# pyra_dvt1_power-2_1.net
KiCad netlist of a schematic drawn in Altium Designer
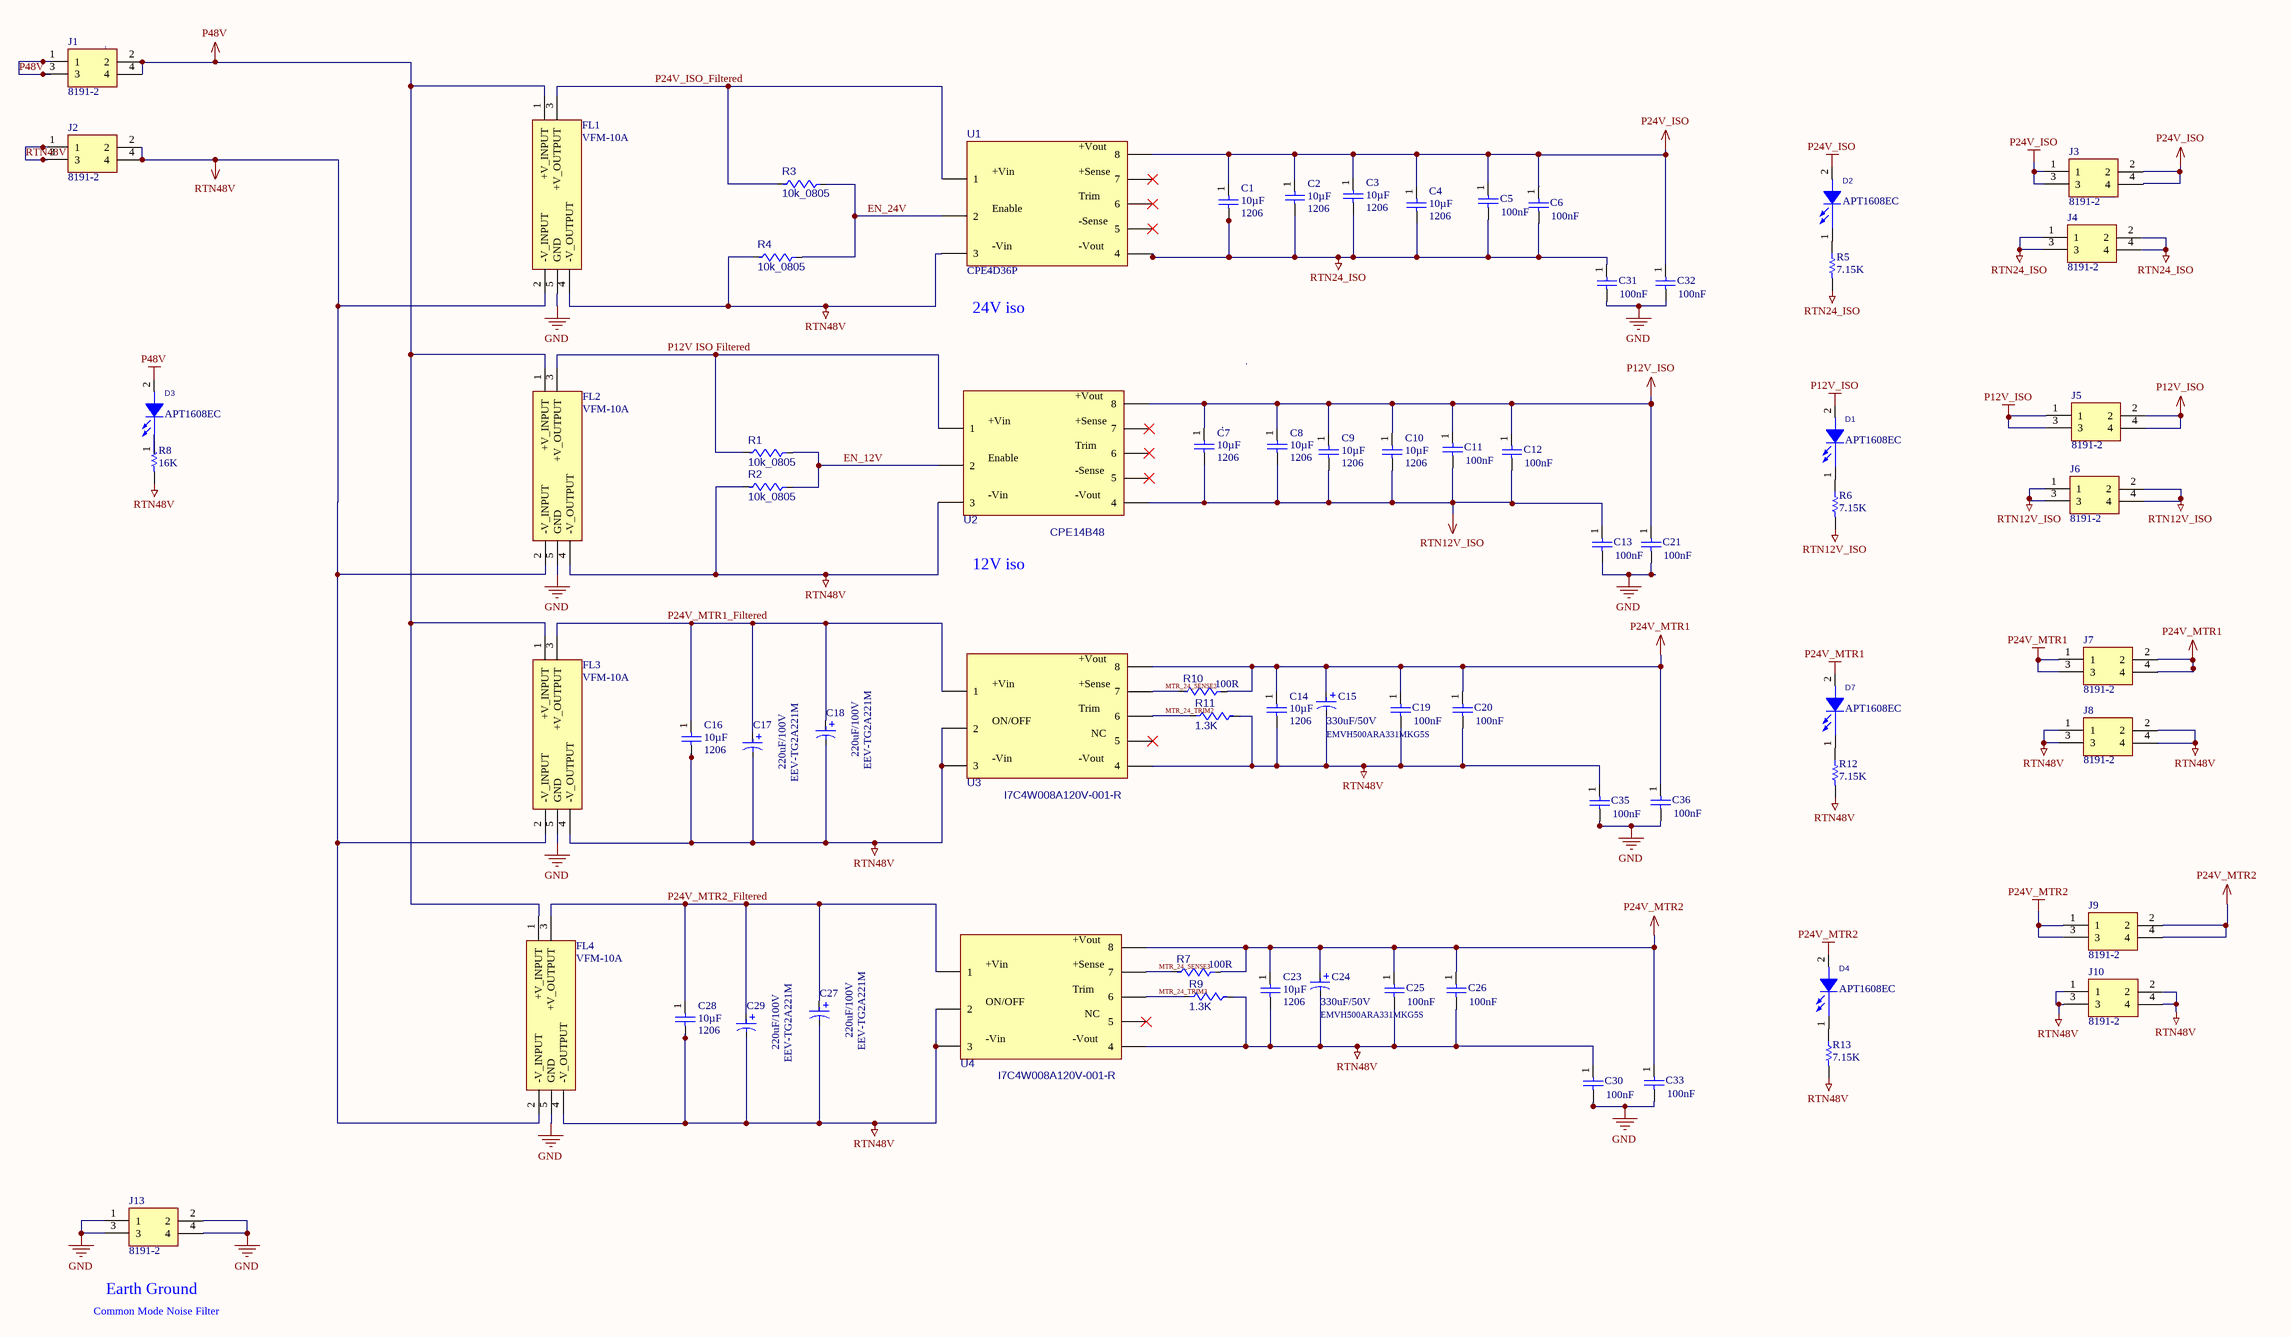
[diagram p0: pyra_dvt1_power-2.1.SchDoc]

(export (version "E")
  (design (tool "Eeschema 10.0.6"))
  (components
    (comp (ref "C1")
      (value "10µF")
      (footprint "1206")
      (description "CAP CER 10UF 50V X5R 1206")
      (fields
        (field (name "MANUFACTURER") "TDK Corporation")
        (field (name "TOLERANCE") "±20%")
        (field (name "SIZE") "1206")
      )
      (libsource (lib "bct") (part "C1206_10UF_50V"))
    )
    (comp (ref "C2")
      (value "10µF")
      (footprint "1206")
      (description "CAP CER 10UF 50V X5R 1206")
      (fields
        (field (name "MANUFACTURER") "TDK Corporation")
        (field (name "TOLERANCE") "±20%")
        (field (name "SIZE") "1206")
      )
      (libsource (lib "bct") (part "C1206_10UF_50V"))
    )
    (comp (ref "C3")
      (value "10µF")
      (footprint "1206")
      (description "CAP CER 10UF 50V X5R 1206")
      (fields
        (field (name "MANUFACTURER") "TDK Corporation")
        (field (name "TOLERANCE") "±20%")
        (field (name "SIZE") "1206")
      )
      (libsource (lib "bct") (part "C1206_10UF_50V"))
    )
    (comp (ref "C4")
      (value "10µF")
      (footprint "1206")
      (description "CAP CER 10UF 50V X5R 1206")
      (fields
        (field (name "MANUFACTURER") "TDK Corporation")
        (field (name "TOLERANCE") "±20%")
        (field (name "SIZE") "1206")
      )
      (libsource (lib "bct") (part "C1206_10UF_50V"))
    )
    (comp (ref "C5")
      (value "100nF")
      (footprint "0603R(1608)")
      (description "CAP CER 0.1UF 50V X5R 0603")
      (fields (field (name "MANUFACTURER") "TDK Corporation") (field (name "TOLERANCE") "±10%"))
      (libsource (lib "bct") (part "C0603_100NF_50V"))
    )
    (comp (ref "C6")
      (value "100nF")
      (footprint "0603R(1608)")
      (description "CAP CER 0.1UF 50V X5R 0603")
      (fields (field (name "MANUFACTURER") "TDK Corporation") (field (name "TOLERANCE") "±10%"))
      (libsource (lib "bct") (part "C0603_100NF_50V"))
    )
    (comp (ref "C7")
      (value "10µF")
      (footprint "1206")
      (description "CAP CER 10UF 50V X5R 1206")
      (fields
        (field (name "MANUFACTURER") "TDK Corporation")
        (field (name "TOLERANCE") "±20%")
        (field (name "SIZE") "1206")
      )
      (libsource (lib "bct") (part "C1206_10UF_50V"))
    )
    (comp (ref "C8")
      (value "10µF")
      (footprint "1206")
      (description "CAP CER 10UF 50V X5R 1206")
      (fields
        (field (name "MANUFACTURER") "TDK Corporation")
        (field (name "TOLERANCE") "±20%")
        (field (name "SIZE") "1206")
      )
      (libsource (lib "bct") (part "C1206_10UF_50V"))
    )
    (comp (ref "C9")
      (value "10µF")
      (footprint "1206")
      (description "CAP CER 10UF 50V X5R 1206")
      (fields
        (field (name "MANUFACTURER") "TDK Corporation")
        (field (name "TOLERANCE") "±20%")
        (field (name "SIZE") "1206")
      )
      (libsource (lib "bct") (part "C1206_10UF_50V"))
    )
    (comp (ref "C10")
      (value "10µF")
      (footprint "1206")
      (description "CAP CER 10UF 50V X5R 1206")
      (fields
        (field (name "MANUFACTURER") "TDK Corporation")
        (field (name "TOLERANCE") "±20%")
        (field (name "SIZE") "1206")
      )
      (libsource (lib "bct") (part "C1206_10UF_50V"))
    )
    (comp (ref "C11")
      (value "100nF")
      (footprint "0603R(1608)")
      (description "CAP CER 0.1UF 50V X5R 0603")
      (fields (field (name "MANUFACTURER") "TDK Corporation") (field (name "TOLERANCE") "±10%"))
      (libsource (lib "bct") (part "C0603_100NF_50V"))
    )
    (comp (ref "C12")
      (value "100nF")
      (footprint "0603R(1608)")
      (description "CAP CER 0.1UF 50V X5R 0603")
      (fields (field (name "MANUFACTURER") "TDK Corporation") (field (name "TOLERANCE") "±10%"))
      (libsource (lib "bct") (part "C0603_100NF_50V"))
    )
    (comp (ref "C13")
      (value "100nF")
      (footprint "0603R(1608)")
      (description "CAP CER 0.1UF 50V X5R 0603")
      (fields (field (name "MANUFACTURER") "TDK Corporation") (field (name "TOLERANCE") "±10%"))
      (libsource (lib "bct") (part "C0603_100NF_50V"))
    )
    (comp (ref "C14")
      (value "10µF")
      (footprint "1206")
      (description "CAP CER 10UF 50V X5R 1206")
      (fields
        (field (name "MANUFACTURER") "TDK Corporation")
        (field (name "TOLERANCE") "±20%")
        (field (name "SIZE") "1206")
      )
      (libsource (lib "bct") (part "C1206_10UF_50V"))
    )
    (comp (ref "C15")
      (value "330uF/50V")
      (footprint "EMVH500ARA331MKG5S")
      (description "CAP ALUM 330UF 20% 50V SMD")
      (fields
        (field (name "MANUFACTURER") "United Chemi-con")
        (field (name "MANUFACTURER PART NUMBER") "EMVH500ARA331MKG5S")
        (field (name "TOLERANCE") "20%")
        (field (name "_VERIFIED FOOTPRINT") ".mfr-pn? footprint?")
        (field (name "_VERIFIED SYMBOL") ".mfr-pn?")
        (field (name "_VERIFIED BOM") ".mfr-pn?")
      )
      (libsource (lib "PowerPCB") (part "CAP POLAR  330uF"))
    )
    (comp (ref "C16")
      (value "10µF")
      (footprint "1206")
      (description "CAP CER 10UF 50V X5R 1206")
      (fields
        (field (name "MANUFACTURER") "TDK Corporation")
        (field (name "TOLERANCE") "±20%")
        (field (name "SIZE") "1206")
      )
      (libsource (lib "bct") (part "C1206_10UF_50V"))
    )
    (comp (ref "C17")
      (value "220uF/100V")
      (footprint "EMVH101GDA221MMN0S")
      (description "CAP ALUM 220UF 20% 100V SMD")
      (fields
        (field (name "MANUFACTURER") "Panasonic")
        (field (name "MANUFACTURER PART NUMBER") "EEV-TG2A221M")
        (field (name "TOLERANCE") "20%")
        (field (name "_VERIFIED FOOTPRINT") ".mfr-pn? footprint?")
        (field (name "_VERIFIED SYMBOL") ".mfr-pn?")
        (field (name "_VERIFIED BOM") ".mfr-pn?")
      )
      (libsource (lib "PowerPCB") (part "CAP POLAR  220uF"))
    )
    (comp (ref "C18")
      (value "220uF/100V")
      (footprint "EMVH101GDA221MMN0S")
      (description "CAP ALUM 220UF 20% 100V SMD")
      (fields
        (field (name "MANUFACTURER") "Panasonic")
        (field (name "MANUFACTURER PART NUMBER") "EEV-TG2A221M")
        (field (name "TOLERANCE") "20%")
        (field (name "_VERIFIED FOOTPRINT") ".mfr-pn? footprint?")
        (field (name "_VERIFIED SYMBOL") ".mfr-pn?")
        (field (name "_VERIFIED BOM") ".mfr-pn?")
      )
      (libsource (lib "PowerPCB") (part "CAP POLAR  220uF"))
    )
    (comp (ref "C19")
      (value "100nF")
      (footprint "0603R(1608)")
      (description "CAP CER 0.1UF 50V X5R 0603")
      (fields (field (name "MANUFACTURER") "TDK Corporation") (field (name "TOLERANCE") "±10%"))
      (libsource (lib "bct") (part "C0603_100NF_50V"))
    )
    (comp (ref "C20")
      (value "100nF")
      (footprint "0603R(1608)")
      (description "CAP CER 0.1UF 50V X5R 0603")
      (fields (field (name "MANUFACTURER") "TDK Corporation") (field (name "TOLERANCE") "±10%"))
      (libsource (lib "bct") (part "C0603_100NF_50V"))
    )
    (comp (ref "C21")
      (value "100nF")
      (footprint "0603R(1608)")
      (description "CAP CER 0.1UF 50V X5R 0603")
      (fields (field (name "MANUFACTURER") "TDK Corporation") (field (name "TOLERANCE") "±10%"))
      (libsource (lib "bct") (part "C0603_100NF_50V"))
    )
    (comp (ref "C23")
      (value "10µF")
      (footprint "1206")
      (description "CAP CER 10UF 50V X5R 1206")
      (fields
        (field (name "MANUFACTURER") "TDK Corporation")
        (field (name "TOLERANCE") "±20%")
        (field (name "SIZE") "1206")
      )
      (libsource (lib "bct") (part "C1206_10UF_50V"))
    )
    (comp (ref "C24")
      (value "330uF/50V")
      (footprint "EMVH500ARA331MKG5S")
      (description "CAP ALUM 330UF 20% 50V SMD")
      (fields
        (field (name "MANUFACTURER") "United Chemi-con")
        (field (name "MANUFACTURER PART NUMBER") "EMVH500ARA331MKG5S")
        (field (name "TOLERANCE") "20%")
        (field (name "_VERIFIED FOOTPRINT") ".mfr-pn? footprint?")
        (field (name "_VERIFIED SYMBOL") ".mfr-pn?")
        (field (name "_VERIFIED BOM") ".mfr-pn?")
      )
      (libsource (lib "PowerPCB") (part "CAP POLAR  330uF"))
    )
    (comp (ref "C25")
      (value "100nF")
      (footprint "0603R(1608)")
      (description "CAP CER 0.1UF 50V X5R 0603")
      (fields (field (name "MANUFACTURER") "TDK Corporation") (field (name "TOLERANCE") "±10%"))
      (libsource (lib "bct") (part "C0603_100NF_50V"))
    )
    (comp (ref "C26")
      (value "100nF")
      (footprint "0603R(1608)")
      (description "CAP CER 0.1UF 50V X5R 0603")
      (fields (field (name "MANUFACTURER") "TDK Corporation") (field (name "TOLERANCE") "±10%"))
      (libsource (lib "bct") (part "C0603_100NF_50V"))
    )
    (comp (ref "C27")
      (value "220uF/100V")
      (footprint "EMVH101GDA221MMN0S")
      (description "CAP ALUM 220UF 20% 100V SMD")
      (fields
        (field (name "MANUFACTURER") "Panasonic")
        (field (name "MANUFACTURER PART NUMBER") "EEV-TG2A221M")
        (field (name "TOLERANCE") "20%")
        (field (name "_VERIFIED FOOTPRINT") ".mfr-pn? footprint?")
        (field (name "_VERIFIED SYMBOL") ".mfr-pn?")
        (field (name "_VERIFIED BOM") ".mfr-pn?")
      )
      (libsource (lib "PowerPCB") (part "CAP POLAR  220uF"))
    )
    (comp (ref "C28")
      (value "10µF")
      (footprint "1206")
      (description "CAP CER 10UF 50V X5R 1206")
      (fields
        (field (name "MANUFACTURER") "TDK Corporation")
        (field (name "TOLERANCE") "±20%")
        (field (name "SIZE") "1206")
      )
      (libsource (lib "bct") (part "C1206_10UF_50V"))
    )
    (comp (ref "C29")
      (value "220uF/100V")
      (footprint "EMVH101GDA221MMN0S")
      (description "CAP ALUM 220UF 20% 100V SMD")
      (fields
        (field (name "MANUFACTURER") "Panasonic")
        (field (name "MANUFACTURER PART NUMBER") "EEV-TG2A221M")
        (field (name "TOLERANCE") "20%")
        (field (name "_VERIFIED FOOTPRINT") ".mfr-pn? footprint?")
        (field (name "_VERIFIED SYMBOL") ".mfr-pn?")
        (field (name "_VERIFIED BOM") ".mfr-pn?")
      )
      (libsource (lib "PowerPCB") (part "CAP POLAR  220uF"))
    )
    (comp (ref "C30")
      (value "100nF")
      (footprint "0603R(1608)")
      (description "CAP CER 0.1UF 50V X5R 0603")
      (fields (field (name "MANUFACTURER") "TDK Corporation") (field (name "TOLERANCE") "±10%"))
      (libsource (lib "bct") (part "C0603_100NF_50V"))
    )
    (comp (ref "C31")
      (value "100nF")
      (footprint "0603R(1608)")
      (description "CAP CER 0.1UF 50V X5R 0603")
      (fields (field (name "MANUFACTURER") "TDK Corporation") (field (name "TOLERANCE") "±10%"))
      (libsource (lib "bct") (part "C0603_100NF_50V"))
    )
    (comp (ref "C32")
      (value "100nF")
      (footprint "0603R(1608)")
      (description "CAP CER 0.1UF 50V X5R 0603")
      (fields (field (name "MANUFACTURER") "TDK Corporation") (field (name "TOLERANCE") "±10%"))
      (libsource (lib "bct") (part "C0603_100NF_50V"))
    )
    (comp (ref "C33")
      (value "100nF")
      (footprint "0603R(1608)")
      (description "CAP CER 0.1UF 50V X5R 0603")
      (fields (field (name "MANUFACTURER") "TDK Corporation") (field (name "TOLERANCE") "±10%"))
      (libsource (lib "bct") (part "C0603_100NF_50V"))
    )
    (comp (ref "C35")
      (value "100nF")
      (footprint "0603R(1608)")
      (description "CAP CER 0.1UF 50V X5R 0603")
      (fields (field (name "MANUFACTURER") "TDK Corporation") (field (name "TOLERANCE") "±10%"))
      (libsource (lib "bct") (part "C0603_100NF_50V"))
    )
    (comp (ref "C36")
      (value "100nF")
      (footprint "0603R(1608)")
      (description "CAP CER 0.1UF 50V X5R 0603")
      (fields (field (name "MANUFACTURER") "TDK Corporation") (field (name "TOLERANCE") "±10%"))
      (libsource (lib "bct") (part "C0603_100NF_50V"))
    )
    (comp (ref "D1")
      (value "APT1608EC")
      (footprint "APT1608EC")
      (description "red, 0603")
      (fields
        (field (name "MANUFACTURER") "Kingbright")
        (field (name "MANUFACTURER PART NUMBER") "APT1608EC")
      )
      (libsource (lib "bct") (part "LED_red_0603"))
    )
    (comp (ref "D2")
      (value "APT1608EC")
      (footprint "APT1608EC")
      (description "red, 0603")
      (fields
        (field (name "MANUFACTURER") "Kingbright")
        (field (name "MANUFACTURER PART NUMBER") "APT1608EC")
      )
      (libsource (lib "bct") (part "LED_red_0603"))
    )
    (comp (ref "D3")
      (value "APT1608EC")
      (footprint "APT1608EC")
      (description "red, 0603")
      (fields
        (field (name "MANUFACTURER") "Kingbright")
        (field (name "MANUFACTURER PART NUMBER") "APT1608EC")
      )
      (libsource (lib "bct") (part "LED_red_0603"))
    )
    (comp (ref "D4")
      (value "APT1608EC")
      (footprint "APT1608EC")
      (description "red, 0603")
      (fields
        (field (name "MANUFACTURER") "Kingbright")
        (field (name "MANUFACTURER PART NUMBER") "APT1608EC")
      )
      (libsource (lib "bct") (part "LED_red_0603"))
    )
    (comp (ref "D7")
      (value "APT1608EC")
      (footprint "APT1608EC")
      (description "red, 0603")
      (fields
        (field (name "MANUFACTURER") "Kingbright")
        (field (name "MANUFACTURER PART NUMBER") "APT1608EC")
      )
      (libsource (lib "bct") (part "LED_red_0603"))
    )
    (comp (ref "FL1")
      (value "VFM-10A")
      (footprint "VFM10A")
      (description "Power Line Filters 0-75Vin 10A DC EMI Filter")
      (fields (field (name "MOUSER PART NUMBER") "490-VFM-10A"))
      (libsource (lib "Bellwether Coffee") (part "VFM-10A"))
    )
    (comp (ref "FL2")
      (value "VFM-10A")
      (footprint "VFM10A")
      (description "Power Line Filters 0-75Vin 10A DC EMI Filter")
      (fields (field (name "MOUSER PART NUMBER") "490-VFM-10A"))
      (libsource (lib "Bellwether Coffee") (part "VFM-10A"))
    )
    (comp (ref "FL3")
      (value "VFM-10A")
      (footprint "VFM10A")
      (description "Power Line Filters 0-75Vin 10A DC EMI Filter")
      (fields (field (name "MOUSER PART NUMBER") "490-VFM-10A"))
      (libsource (lib "Bellwether Coffee") (part "VFM-10A"))
    )
    (comp (ref "FL4")
      (value "VFM-10A")
      (footprint "VFM10A")
      (description "Power Line Filters 0-75Vin 10A DC EMI Filter")
      (fields (field (name "MOUSER PART NUMBER") "490-VFM-10A"))
      (libsource (lib "Bellwether Coffee") (part "VFM-10A"))
    )
    (comp (ref "J1")
      (value "8191-2")
      (footprint "81912")
      (description "Keystone, Brass Screw Terminal, 22  14 AWG, 15A")
      (fields (field (name "MOUSER PART NUMBER") "534-8191-2"))
      (libsource (lib "Bellwether Coffee") (part "8191-2"))
    )
    (comp (ref "J2")
      (value "8191-2")
      (footprint "81912")
      (description "Keystone, Brass Screw Terminal, 22  14 AWG, 15A")
      (fields (field (name "MOUSER PART NUMBER") "534-8191-2"))
      (libsource (lib "Bellwether Coffee") (part "8191-2"))
    )
    (comp (ref "J3")
      (value "8191-2")
      (footprint "81912")
      (description "Keystone, Brass Screw Terminal, 22  14 AWG, 15A")
      (fields (field (name "MOUSER PART NUMBER") "534-8191-2"))
      (libsource (lib "Bellwether Coffee") (part "8191-2"))
    )
    (comp (ref "J4")
      (value "8191-2")
      (footprint "81912")
      (description "Keystone, Brass Screw Terminal, 22  14 AWG, 15A")
      (fields (field (name "MOUSER PART NUMBER") "534-8191-2"))
      (libsource (lib "Bellwether Coffee") (part "8191-2"))
    )
    (comp (ref "J5")
      (value "8191-2")
      (footprint "81912")
      (description "Keystone, Brass Screw Terminal, 22  14 AWG, 15A")
      (fields (field (name "MOUSER PART NUMBER") "534-8191-2"))
      (libsource (lib "Bellwether Coffee") (part "8191-2"))
    )
    (comp (ref "J6")
      (value "8191-2")
      (footprint "81912")
      (description "Keystone, Brass Screw Terminal, 22  14 AWG, 15A")
      (fields (field (name "MOUSER PART NUMBER") "534-8191-2"))
      (libsource (lib "Bellwether Coffee") (part "8191-2"))
    )
    (comp (ref "J7")
      (value "8191-2")
      (footprint "81912")
      (description "Keystone, Brass Screw Terminal, 22  14 AWG, 15A")
      (fields (field (name "MOUSER PART NUMBER") "534-8191-2"))
      (libsource (lib "Bellwether Coffee") (part "8191-2"))
    )
    (comp (ref "J8")
      (value "8191-2")
      (footprint "81912")
      (description "Keystone, Brass Screw Terminal, 22  14 AWG, 15A")
      (fields (field (name "MOUSER PART NUMBER") "534-8191-2"))
      (libsource (lib "Bellwether Coffee") (part "8191-2"))
    )
    (comp (ref "J9")
      (value "8191-2")
      (footprint "81912")
      (description "Keystone, Brass Screw Terminal, 22  14 AWG, 15A")
      (fields (field (name "MOUSER PART NUMBER") "534-8191-2"))
      (libsource (lib "Bellwether Coffee") (part "8191-2"))
    )
    (comp (ref "J10")
      (value "8191-2")
      (footprint "81912")
      (description "Keystone, Brass Screw Terminal, 22  14 AWG, 15A")
      (fields (field (name "MOUSER PART NUMBER") "534-8191-2"))
      (libsource (lib "Bellwether Coffee") (part "8191-2"))
    )
    (comp (ref "J13")
      (value "8191-2")
      (footprint "81912")
      (description "Keystone, Brass Screw Terminal, 22  14 AWG, 15A")
      (fields (field (name "MOUSER PART NUMBER") "534-8191-2"))
      (libsource (lib "Bellwether Coffee") (part "8191-2"))
    )
    (comp (ref "R1")
      (value "10k_0805")
      (footprint "0805")
      (description "Res Thick Film 0805 10K Ohm 1% 0.125W ±100ppm/°C Molded SMD Paper T/R")
      (fields
        (field (name "MANUFACTURER") "Stackpole Electronics")
        (field (name "MANUFACTURER PART NUMBER") "RMCF0805FT10K0")
      )
      (libsource (lib "PowerPCB") (part "RES 10k_0805"))
    )
    (comp (ref "R2")
      (value "10k_0805")
      (footprint "0805")
      (description "Res Thick Film 0805 10K Ohm 1% 0.125W ±100ppm/°C Molded SMD Paper T/R")
      (fields
        (field (name "MANUFACTURER") "Stackpole Electronics")
        (field (name "MANUFACTURER PART NUMBER") "RMCF0805FT10K0")
      )
      (libsource (lib "PowerPCB") (part "RES 10k_0805"))
    )
    (comp (ref "R3")
      (value "10k_0805")
      (footprint "0805")
      (description "Res Thick Film 0805 10K Ohm 1% 0.125W ±100ppm/°C Molded SMD Paper T/R")
      (fields
        (field (name "MANUFACTURER") "Stackpole Electronics")
        (field (name "MANUFACTURER PART NUMBER") "RMCF0805FT10K0")
      )
      (libsource (lib "PowerPCB") (part "RES 10k_0805"))
    )
    (comp (ref "R4")
      (value "10k_0805")
      (footprint "0805")
      (description "Res Thick Film 0805 10K Ohm 1% 0.125W ±100ppm/°C Molded SMD Paper T/R")
      (fields
        (field (name "MANUFACTURER") "Stackpole Electronics")
        (field (name "MANUFACTURER PART NUMBER") "RMCF0805FT10K0")
      )
      (libsource (lib "PowerPCB") (part "RES 10k_0805"))
    )
    (comp (ref "R5")
      (value "10k")
      (footprint "0603R(1608)")
      (description "RES SMD 10K OHM 5% 1/10W 0603")
      (fields
        (field (name "TOLERANCE") "±1%")
        (field (name "MANUFACTURER") "Panasonic Electronic Components")
        (field (name "RESISTANCE (OHMS)") "7.15K")
      )
      (libsource (lib "Control_1") (part "RES-0603-10K_1"))
    )
    (comp (ref "R6")
      (value "10k")
      (footprint "0603R(1608)")
      (description "RES SMD 10K OHM 5% 1/10W 0603")
      (fields
        (field (name "TOLERANCE") "±1%")
        (field (name "MANUFACTURER") "Panasonic Electronic Components")
        (field (name "RESISTANCE (OHMS)") "7.15K")
      )
      (libsource (lib "Control_1") (part "RES-0603-10K_1"))
    )
    (comp (ref "R7")
      (value "?")
      (footprint "0805")
      (description "RES 100 OHM 5% 1/4W 0805")
      (fields
        (field (name "MANUFACTURER") "KOA")
        (field (name "MANUFACTURER PART NUMBER") "RK73B2ATTD101J")
        (field (name "RESISTANCE") "100R")
        (field (name "_VERIFIED FOOTPRINT") ".mfr-pn? footprint?")
        (field (name "_VERIFIED BOM") ".mfr-pn?")
        (field (name "_VERIFIED SYMBOL") ".mfr-pn?")
      )
      (libsource (lib "Generics-MT") (part "RES .val? 0805"))
    )
    (comp (ref "R8")
      (value "10k")
      (footprint "0603R(1608)")
      (description "RES SMD 10K OHM 5% 1/10W 0603")
      (fields
        (field (name "TOLERANCE") "±1%")
        (field (name "MANUFACTURER") "Panasonic Electronic Components")
        (field (name "RESISTANCE (OHMS)") "16K")
      )
      (libsource (lib "Control_1") (part "RES-0603-10K_1"))
    )
    (comp (ref "R9")
      (value "1.3K")
      (footprint "0603R(1608)")
      (description "RES SMD 1.3K OHM 1% 1/10W 0603")
      (fields
        (field (name "MANUFACTURER") "Panasonic")
        (field (name "MANUFACTURER PART NUMBER") "ERJ-3EKF1301V")
        (field (name "_VERIFIED FOOTPRINT") ".mfr-pn? footprint?")
        (field (name "_VERIFIED SYMBOL") ".mfr-pn?")
        (field (name "_VERIFIED BOM") ".mfr-pn?")
      )
      (libsource (lib "Generics-MT") (part "RES .val? .pkg?"))
    )
    (comp (ref "R10")
      (value "?")
      (footprint "0805")
      (description "RES 100 OHM 5% 1/4W 0805")
      (fields
        (field (name "MANUFACTURER") "KOA")
        (field (name "MANUFACTURER PART NUMBER") "RK73B2ATTD101J")
        (field (name "RESISTANCE") "100R")
        (field (name "_VERIFIED FOOTPRINT") ".mfr-pn? footprint?")
        (field (name "_VERIFIED BOM") ".mfr-pn?")
        (field (name "_VERIFIED SYMBOL") ".mfr-pn?")
      )
      (libsource (lib "Generics-MT") (part "RES .val? 0805"))
    )
    (comp (ref "R11")
      (value "1.3K")
      (footprint "0603R(1608)")
      (description "RES SMD 1.3K OHM 1% 1/10W 0603")
      (fields
        (field (name "MANUFACTURER") "Panasonic")
        (field (name "MANUFACTURER PART NUMBER") "ERJ-3EKF1301V")
        (field (name "_VERIFIED FOOTPRINT") ".mfr-pn? footprint?")
        (field (name "_VERIFIED SYMBOL") ".mfr-pn?")
        (field (name "_VERIFIED BOM") ".mfr-pn?")
      )
      (libsource (lib "Generics-MT") (part "RES .val? .pkg?"))
    )
    (comp (ref "R12")
      (value "10k")
      (footprint "0603R(1608)")
      (description "RES SMD 10K OHM 5% 1/10W 0603")
      (fields
        (field (name "TOLERANCE") "±1%")
        (field (name "MANUFACTURER") "Panasonic Electronic Components")
        (field (name "RESISTANCE (OHMS)") "7.15K")
      )
      (libsource (lib "Control_1") (part "RES-0603-10K_1"))
    )
    (comp (ref "R13")
      (value "10k")
      (footprint "0603R(1608)")
      (description "RES SMD 10K OHM 5% 1/10W 0603")
      (fields
        (field (name "TOLERANCE") "±1%")
        (field (name "MANUFACTURER") "Panasonic Electronic Components")
        (field (name "RESISTANCE (OHMS)") "7.15K")
      )
      (libsource (lib "Control_1") (part "RES-0603-10K_1"))
    )
    (comp (ref "U1")
      (value "CPE4D36P")
      (footprint "CPE4D36N")
      (description "Isolated Module DC DC Converter 1 Output 24V    4A 18V - 72V Input")
      (fields
        (field (name "MANUFACTURER") "Semiconductor Circuits, Inc.")
        (field (name "MANUFACTURER PART NUMBER") "CPE4D36P")
        (field (name "MANUFACTURER2 PART NUMBER") "ERS3240N004N25W")
      )
      (libsource (lib "PowerPCB") (part "CPE4D36N"))
    )
    (comp (ref "U2")
      (value "CPE14B48")
      (footprint "CPE4D36N")
      (description "Isolated Module DC DC Converter 1 Output 12V    14A 36V - 75V Input")
      (fields
        (field (name "MANUFACTURER") "Semiconductor Circuits, Inc.")
        (field (name "MANUFACTURER PART NUMBER") "CPE14B48P")
      )
      (libsource (lib "PowerPCB") (part "CPE8B48P"))
    )
    (comp (ref "U3")
      (value "I7C4W008A120V-001-R")
      (footprint "CPT2D36P")
      (description "DC DC CONVERTER 9.6-48V OUTPUT 300W 8A 9V - 53V INPUT")
      (fields (field (name "MANUFACTURER") "TDK-Lambda"))
      (libsource (lib "PowerPCB") (part "I7C4W008A120V-001-R"))
    )
    (comp (ref "U4")
      (value "I7C4W008A120V-001-R")
      (footprint "CPT2D36P")
      (description "DC DC CONVERTER 9.6-48V OUTPUT 300W 8A 9V - 53V INPUT")
      (fields (field (name "MANUFACTURER") "TDK-Lambda"))
      (libsource (lib "PowerPCB") (part "I7C4W008A120V-001-R"))
    )
  )
  (nets
    (net (code "1") (name "/EN_12V") (class "Default")
      (node (ref "R1") (pin "2") (pinfunction "2_2") (pintype "passive"))
      (node (ref "R2") (pin "2") (pinfunction "2_2") (pintype "passive"))
      (node (ref "U2") (pin "2") (pinfunction "2_2") (pintype "passive"))
    )
    (net (code "2") (name "/EN_24V") (class "Default")
      (node (ref "R3") (pin "2") (pinfunction "2_2") (pintype "passive"))
      (node (ref "R4") (pin "2") (pinfunction "2_2") (pintype "passive"))
      (node (ref "U1") (pin "2") (pinfunction "2_2") (pintype "passive"))
    )
    (net (code "3") (name "/MTR_24_SENSE2") (class "Default")
      (node (ref "R10") (pin "1") (pinfunction "1_1") (pintype "passive"))
      (node (ref "U3") (pin "7") (pinfunction "7_7") (pintype "passive"))
    )
    (net (code "4") (name "/MTR_24_SENSE3") (class "Default")
      (node (ref "R7") (pin "1") (pinfunction "1_1") (pintype "passive"))
      (node (ref "U4") (pin "7") (pinfunction "7_7") (pintype "passive"))
    )
    (net (code "5") (name "/MTR_24_TRIM2") (class "Default")
      (node (ref "R11") (pin "2") (pinfunction "2_2") (pintype "passive"))
      (node (ref "U3") (pin "6") (pinfunction "6_6") (pintype "passive"))
    )
    (net (code "6") (name "/MTR_24_TRIM3") (class "Default")
      (node (ref "R9") (pin "2") (pinfunction "2_2") (pintype "passive"))
      (node (ref "U4") (pin "6") (pinfunction "6_6") (pintype "passive"))
    )
    (net (code "7") (name "/P12V ISO Filtered") (class "Default")
      (node (ref "FL2") (pin "3") (pinfunction "+V_OUTPUT_3") (pintype "passive"))
      (node (ref "R1") (pin "1") (pinfunction "1_1") (pintype "passive"))
      (node (ref "U2") (pin "1") (pinfunction "1_1") (pintype "passive"))
    )
    (net (code "8") (name "/P24V_ISO_Filtered") (class "Default")
      (node (ref "FL1") (pin "3") (pinfunction "+V_OUTPUT_3") (pintype "passive"))
      (node (ref "R3") (pin "1") (pinfunction "1_1") (pintype "passive"))
      (node (ref "U1") (pin "1") (pinfunction "1_1") (pintype "passive"))
    )
    (net (code "9") (name "/P24V_MTR1_Filtered") (class "Default")
      (node (ref "C16") (pin "1") (pinfunction "1_1") (pintype "passive"))
      (node (ref "C17") (pin "1") (pinfunction "1_1") (pintype "passive"))
      (node (ref "C18") (pin "1") (pinfunction "1_1") (pintype "passive"))
      (node (ref "FL3") (pin "3") (pinfunction "+V_OUTPUT_3") (pintype "passive"))
      (node (ref "U3") (pin "1") (pinfunction "1_1") (pintype "passive"))
    )
    (net (code "10") (name "/P24V_MTR2_Filtered") (class "Default")
      (node (ref "C27") (pin "1") (pinfunction "1_1") (pintype "passive"))
      (node (ref "C28") (pin "1") (pinfunction "1_1") (pintype "passive"))
      (node (ref "C29") (pin "1") (pinfunction "1_1") (pintype "passive"))
      (node (ref "FL4") (pin "3") (pinfunction "+V_OUTPUT_3") (pintype "passive"))
      (node (ref "U4") (pin "1") (pinfunction "1_1") (pintype "passive"))
    )
    (net (code "11") (name "GND") (class "Default")
      (node (ref "C13") (pin "2") (pinfunction "2_2") (pintype "passive"))
      (node (ref "C21") (pin "2") (pinfunction "2_2") (pintype "passive"))
      (node (ref "C30") (pin "2") (pinfunction "2_2") (pintype "passive"))
      (node (ref "C31") (pin "2") (pinfunction "2_2") (pintype "passive"))
      (node (ref "C32") (pin "2") (pinfunction "2_2") (pintype "passive"))
      (node (ref "C33") (pin "2") (pinfunction "2_2") (pintype "passive"))
      (node (ref "C35") (pin "2") (pinfunction "2_2") (pintype "passive"))
      (node (ref "C36") (pin "2") (pinfunction "2_2") (pintype "passive"))
      (node (ref "FL1") (pin "5") (pinfunction "GND_5") (pintype "passive"))
      (node (ref "FL2") (pin "5") (pinfunction "GND_5") (pintype "passive"))
      (node (ref "FL3") (pin "5") (pinfunction "GND_5") (pintype "passive"))
      (node (ref "FL4") (pin "5") (pinfunction "GND_5") (pintype "passive"))
      (node (ref "J13") (pin "1") (pinfunction "1_1") (pintype "passive"))
      (node (ref "J13") (pin "2") (pinfunction "2_2") (pintype "passive"))
      (node (ref "J13") (pin "3") (pinfunction "3_3") (pintype "passive"))
      (node (ref "J13") (pin "4") (pinfunction "4_4") (pintype "passive"))
    )
    (net (code "12") (name "Net-(D1-CATHODE)") (class "Default")
      (node (ref "D1") (pin "1") (pinfunction "CATHODE_1") (pintype "passive"))
      (node (ref "R6") (pin "1") (pinfunction "1_1") (pintype "passive"))
    )
    (net (code "13") (name "Net-(D2-CATHODE)") (class "Default")
      (node (ref "D2") (pin "1") (pinfunction "CATHODE_1") (pintype "passive"))
      (node (ref "R5") (pin "1") (pinfunction "1_1") (pintype "passive"))
    )
    (net (code "14") (name "Net-(D3-CATHODE)") (class "Default")
      (node (ref "D3") (pin "1") (pinfunction "CATHODE_1") (pintype "passive"))
      (node (ref "R8") (pin "1") (pinfunction "1_1") (pintype "passive"))
    )
    (net (code "15") (name "Net-(D4-CATHODE)") (class "Default")
      (node (ref "D4") (pin "1") (pinfunction "CATHODE_1") (pintype "passive"))
      (node (ref "R13") (pin "1") (pinfunction "1_1") (pintype "passive"))
    )
    (net (code "16") (name "Net-(D7-CATHODE)") (class "Default")
      (node (ref "D7") (pin "1") (pinfunction "CATHODE_1") (pintype "passive"))
      (node (ref "R12") (pin "1") (pinfunction "1_1") (pintype "passive"))
    )
    (net (code "17") (name "P12V_ISO") (class "Default")
      (node (ref "C10") (pin "1") (pinfunction "1_1") (pintype "passive"))
      (node (ref "C11") (pin "1") (pinfunction "1_1") (pintype "passive"))
      (node (ref "C12") (pin "1") (pinfunction "1_1") (pintype "passive"))
      (node (ref "C21") (pin "1") (pinfunction "1_1") (pintype "passive"))
      (node (ref "C7") (pin "1") (pinfunction "1_1") (pintype "passive"))
      (node (ref "C8") (pin "1") (pinfunction "1_1") (pintype "passive"))
      (node (ref "C9") (pin "1") (pinfunction "1_1") (pintype "passive"))
      (node (ref "D1") (pin "2") (pinfunction "ANODE_2") (pintype "passive"))
      (node (ref "J5") (pin "1") (pinfunction "1_1") (pintype "passive"))
      (node (ref "J5") (pin "2") (pinfunction "2_2") (pintype "passive"))
      (node (ref "J5") (pin "3") (pinfunction "3_3") (pintype "passive"))
      (node (ref "J5") (pin "4") (pinfunction "4_4") (pintype "passive"))
      (node (ref "U2") (pin "8") (pinfunction "8_8") (pintype "passive"))
    )
    (net (code "18") (name "P24V_ISO") (class "Default")
      (node (ref "C1") (pin "1") (pinfunction "1_1") (pintype "passive"))
      (node (ref "C2") (pin "1") (pinfunction "1_1") (pintype "passive"))
      (node (ref "C3") (pin "1") (pinfunction "1_1") (pintype "passive"))
      (node (ref "C32") (pin "1") (pinfunction "1_1") (pintype "passive"))
      (node (ref "C4") (pin "1") (pinfunction "1_1") (pintype "passive"))
      (node (ref "C5") (pin "1") (pinfunction "1_1") (pintype "passive"))
      (node (ref "C6") (pin "1") (pinfunction "1_1") (pintype "passive"))
      (node (ref "D2") (pin "2") (pinfunction "ANODE_2") (pintype "passive"))
      (node (ref "J3") (pin "1") (pinfunction "1_1") (pintype "passive"))
      (node (ref "J3") (pin "2") (pinfunction "2_2") (pintype "passive"))
      (node (ref "J3") (pin "3") (pinfunction "3_3") (pintype "passive"))
      (node (ref "J3") (pin "4") (pinfunction "4_4") (pintype "passive"))
      (node (ref "U1") (pin "8") (pinfunction "8_8") (pintype "passive"))
    )
    (net (code "19") (name "P24V_MTR1") (class "Default")
      (node (ref "C14") (pin "1") (pinfunction "1_1") (pintype "passive"))
      (node (ref "C15") (pin "1") (pinfunction "1_1") (pintype "passive"))
      (node (ref "C19") (pin "1") (pinfunction "1_1") (pintype "passive"))
      (node (ref "C20") (pin "1") (pinfunction "1_1") (pintype "passive"))
      (node (ref "C36") (pin "1") (pinfunction "1_1") (pintype "passive"))
      (node (ref "D7") (pin "2") (pinfunction "ANODE_2") (pintype "passive"))
      (node (ref "J7") (pin "1") (pinfunction "1_1") (pintype "passive"))
      (node (ref "J7") (pin "2") (pinfunction "2_2") (pintype "passive"))
      (node (ref "J7") (pin "3") (pinfunction "3_3") (pintype "passive"))
      (node (ref "J7") (pin "4") (pinfunction "4_4") (pintype "passive"))
      (node (ref "R10") (pin "2") (pinfunction "2_2") (pintype "passive"))
      (node (ref "U3") (pin "8") (pinfunction "8_8") (pintype "passive"))
    )
    (net (code "20") (name "P24V_MTR2") (class "Default")
      (node (ref "C23") (pin "1") (pinfunction "1_1") (pintype "passive"))
      (node (ref "C24") (pin "1") (pinfunction "1_1") (pintype "passive"))
      (node (ref "C25") (pin "1") (pinfunction "1_1") (pintype "passive"))
      (node (ref "C26") (pin "1") (pinfunction "1_1") (pintype "passive"))
      (node (ref "C33") (pin "1") (pinfunction "1_1") (pintype "passive"))
      (node (ref "D4") (pin "2") (pinfunction "ANODE_2") (pintype "passive"))
      (node (ref "J9") (pin "1") (pinfunction "1_1") (pintype "passive"))
      (node (ref "J9") (pin "2") (pinfunction "2_2") (pintype "passive"))
      (node (ref "J9") (pin "3") (pinfunction "3_3") (pintype "passive"))
      (node (ref "J9") (pin "4") (pinfunction "4_4") (pintype "passive"))
      (node (ref "R7") (pin "2") (pinfunction "2_2") (pintype "passive"))
      (node (ref "U4") (pin "8") (pinfunction "8_8") (pintype "passive"))
    )
    (net (code "21") (name "P48V") (class "Default")
      (node (ref "D3") (pin "2") (pinfunction "ANODE_2") (pintype "passive"))
      (node (ref "FL1") (pin "1") (pinfunction "+V_INPUT_1") (pintype "passive"))
      (node (ref "FL2") (pin "1") (pinfunction "+V_INPUT_1") (pintype "passive"))
      (node (ref "FL3") (pin "1") (pinfunction "+V_INPUT_1") (pintype "passive"))
      (node (ref "FL4") (pin "1") (pinfunction "+V_INPUT_1") (pintype "passive"))
      (node (ref "J1") (pin "1") (pinfunction "1_1") (pintype "passive"))
      (node (ref "J1") (pin "2") (pinfunction "2_2") (pintype "passive"))
      (node (ref "J1") (pin "3") (pinfunction "3_3") (pintype "passive"))
      (node (ref "J1") (pin "4") (pinfunction "4_4") (pintype "passive"))
    )
    (net (code "22") (name "RTN12V_ISO") (class "Default")
      (node (ref "C10") (pin "2") (pinfunction "2_2") (pintype "passive"))
      (node (ref "C11") (pin "2") (pinfunction "2_2") (pintype "passive"))
      (node (ref "C12") (pin "2") (pinfunction "2_2") (pintype "passive"))
      (node (ref "C13") (pin "1") (pinfunction "1_1") (pintype "passive"))
      (node (ref "C7") (pin "2") (pinfunction "2_2") (pintype "passive"))
      (node (ref "C8") (pin "2") (pinfunction "2_2") (pintype "passive"))
      (node (ref "C9") (pin "2") (pinfunction "2_2") (pintype "passive"))
      (node (ref "J6") (pin "1") (pinfunction "1_1") (pintype "passive"))
      (node (ref "J6") (pin "2") (pinfunction "2_2") (pintype "passive"))
      (node (ref "J6") (pin "3") (pinfunction "3_3") (pintype "passive"))
      (node (ref "J6") (pin "4") (pinfunction "4_4") (pintype "passive"))
      (node (ref "R6") (pin "2") (pinfunction "2_2") (pintype "passive"))
      (node (ref "U2") (pin "4") (pinfunction "4_4") (pintype "passive"))
    )
    (net (code "23") (name "RTN24_ISO") (class "Default")
      (node (ref "C1") (pin "2") (pinfunction "2_2") (pintype "passive"))
      (node (ref "C2") (pin "2") (pinfunction "2_2") (pintype "passive"))
      (node (ref "C3") (pin "2") (pinfunction "2_2") (pintype "passive"))
      (node (ref "C31") (pin "1") (pinfunction "1_1") (pintype "passive"))
      (node (ref "C4") (pin "2") (pinfunction "2_2") (pintype "passive"))
      (node (ref "C5") (pin "2") (pinfunction "2_2") (pintype "passive"))
      (node (ref "C6") (pin "2") (pinfunction "2_2") (pintype "passive"))
      (node (ref "J4") (pin "1") (pinfunction "1_1") (pintype "passive"))
      (node (ref "J4") (pin "2") (pinfunction "2_2") (pintype "passive"))
      (node (ref "J4") (pin "3") (pinfunction "3_3") (pintype "passive"))
      (node (ref "J4") (pin "4") (pinfunction "4_4") (pintype "passive"))
      (node (ref "R5") (pin "2") (pinfunction "2_2") (pintype "passive"))
      (node (ref "U1") (pin "4") (pinfunction "4_4") (pintype "passive"))
    )
    (net (code "24") (name "RTN48V") (class "Default")
      (node (ref "C14") (pin "2") (pinfunction "2_2") (pintype "passive"))
      (node (ref "C15") (pin "2") (pinfunction "2_2") (pintype "passive"))
      (node (ref "C16") (pin "2") (pinfunction "2_2") (pintype "passive"))
      (node (ref "C17") (pin "2") (pinfunction "2_2") (pintype "passive"))
      (node (ref "C18") (pin "2") (pinfunction "2_2") (pintype "passive"))
      (node (ref "C19") (pin "2") (pinfunction "2_2") (pintype "passive"))
      (node (ref "C20") (pin "2") (pinfunction "2_2") (pintype "passive"))
      (node (ref "C23") (pin "2") (pinfunction "2_2") (pintype "passive"))
      (node (ref "C24") (pin "2") (pinfunction "2_2") (pintype "passive"))
      (node (ref "C25") (pin "2") (pinfunction "2_2") (pintype "passive"))
      (node (ref "C26") (pin "2") (pinfunction "2_2") (pintype "passive"))
      (node (ref "C27") (pin "2") (pinfunction "2_2") (pintype "passive"))
      (node (ref "C28") (pin "2") (pinfunction "2_2") (pintype "passive"))
      (node (ref "C29") (pin "2") (pinfunction "2_2") (pintype "passive"))
      (node (ref "C30") (pin "1") (pinfunction "1_1") (pintype "passive"))
      (node (ref "C35") (pin "1") (pinfunction "1_1") (pintype "passive"))
      (node (ref "FL1") (pin "2") (pinfunction "-V_INPUT_2") (pintype "passive"))
      (node (ref "FL1") (pin "4") (pinfunction "-V_OUTPUT_4") (pintype "passive"))
      (node (ref "FL2") (pin "2") (pinfunction "-V_INPUT_2") (pintype "passive"))
      (node (ref "FL2") (pin "4") (pinfunction "-V_OUTPUT_4") (pintype "passive"))
      (node (ref "FL3") (pin "2") (pinfunction "-V_INPUT_2") (pintype "passive"))
      (node (ref "FL3") (pin "4") (pinfunction "-V_OUTPUT_4") (pintype "passive"))
      (node (ref "FL4") (pin "2") (pinfunction "-V_INPUT_2") (pintype "passive"))
      (node (ref "FL4") (pin "4") (pinfunction "-V_OUTPUT_4") (pintype "passive"))
      (node (ref "J10") (pin "1") (pinfunction "1_1") (pintype "passive"))
      (node (ref "J10") (pin "2") (pinfunction "2_2") (pintype "passive"))
      (node (ref "J10") (pin "3") (pinfunction "3_3") (pintype "passive"))
      (node (ref "J10") (pin "4") (pinfunction "4_4") (pintype "passive"))
      (node (ref "J2") (pin "1") (pinfunction "1_1") (pintype "passive"))
      (node (ref "J2") (pin "2") (pinfunction "2_2") (pintype "passive"))
      (node (ref "J2") (pin "3") (pinfunction "3_3") (pintype "passive"))
      (node (ref "J2") (pin "4") (pinfunction "4_4") (pintype "passive"))
      (node (ref "J8") (pin "1") (pinfunction "1_1") (pintype "passive"))
      (node (ref "J8") (pin "2") (pinfunction "2_2") (pintype "passive"))
      (node (ref "J8") (pin "3") (pinfunction "3_3") (pintype "passive"))
      (node (ref "J8") (pin "4") (pinfunction "4_4") (pintype "passive"))
      (node (ref "R11") (pin "1") (pinfunction "1_1") (pintype "passive"))
      (node (ref "R12") (pin "2") (pinfunction "2_2") (pintype "passive"))
      (node (ref "R13") (pin "2") (pinfunction "2_2") (pintype "passive"))
      (node (ref "R2") (pin "1") (pinfunction "1_1") (pintype "passive"))
      (node (ref "R4") (pin "1") (pinfunction "1_1") (pintype "passive"))
      (node (ref "R8") (pin "2") (pinfunction "2_2") (pintype "passive"))
      (node (ref "R9") (pin "1") (pinfunction "1_1") (pintype "passive"))
      (node (ref "U1") (pin "3") (pinfunction "3_3") (pintype "passive"))
      (node (ref "U2") (pin "3") (pinfunction "3_3") (pintype "passive"))
      (node (ref "U3") (pin "2") (pinfunction "2_2") (pintype "passive"))
      (node (ref "U3") (pin "3") (pinfunction "3_3") (pintype "passive"))
      (node (ref "U3") (pin "4") (pinfunction "4_4") (pintype "passive"))
      (node (ref "U4") (pin "2") (pinfunction "2_2") (pintype "passive"))
      (node (ref "U4") (pin "3") (pinfunction "3_3") (pintype "passive"))
      (node (ref "U4") (pin "4") (pinfunction "4_4") (pintype "passive"))
    )
    (net (code "25") (name "unconnected-(U1-Pad5)") (class "Default")
      (node (ref "U1") (pin "5") (pinfunction "5_5") (pintype "passive+no_connect"))
    )
    (net (code "26") (name "unconnected-(U1-Pad6)") (class "Default")
      (node (ref "U1") (pin "6") (pinfunction "6_6") (pintype "passive+no_connect"))
    )
    (net (code "27") (name "unconnected-(U1-Pad7)") (class "Default")
      (node (ref "U1") (pin "7") (pinfunction "7_7") (pintype "passive+no_connect"))
    )
    (net (code "28") (name "unconnected-(U2-Pad5)") (class "Default")
      (node (ref "U2") (pin "5") (pinfunction "5_5") (pintype "passive+no_connect"))
    )
    (net (code "29") (name "unconnected-(U2-Pad6)") (class "Default")
      (node (ref "U2") (pin "6") (pinfunction "6_6") (pintype "passive+no_connect"))
    )
    (net (code "30") (name "unconnected-(U2-Pad7)") (class "Default")
      (node (ref "U2") (pin "7") (pinfunction "7_7") (pintype "passive+no_connect"))
    )
    (net (code "31") (name "unconnected-(U3-Pad5)") (class "Default")
      (node (ref "U3") (pin "5") (pinfunction "5_5") (pintype "passive+no_connect"))
    )
    (net (code "32") (name "unconnected-(U4-Pad5)") (class "Default")
      (node (ref "U4") (pin "5") (pinfunction "5_5") (pintype "passive+no_connect"))
    )
  )
)
